# STM32_Decoupling.net
KiCad netlist of a schematic drawn in Altium Designer
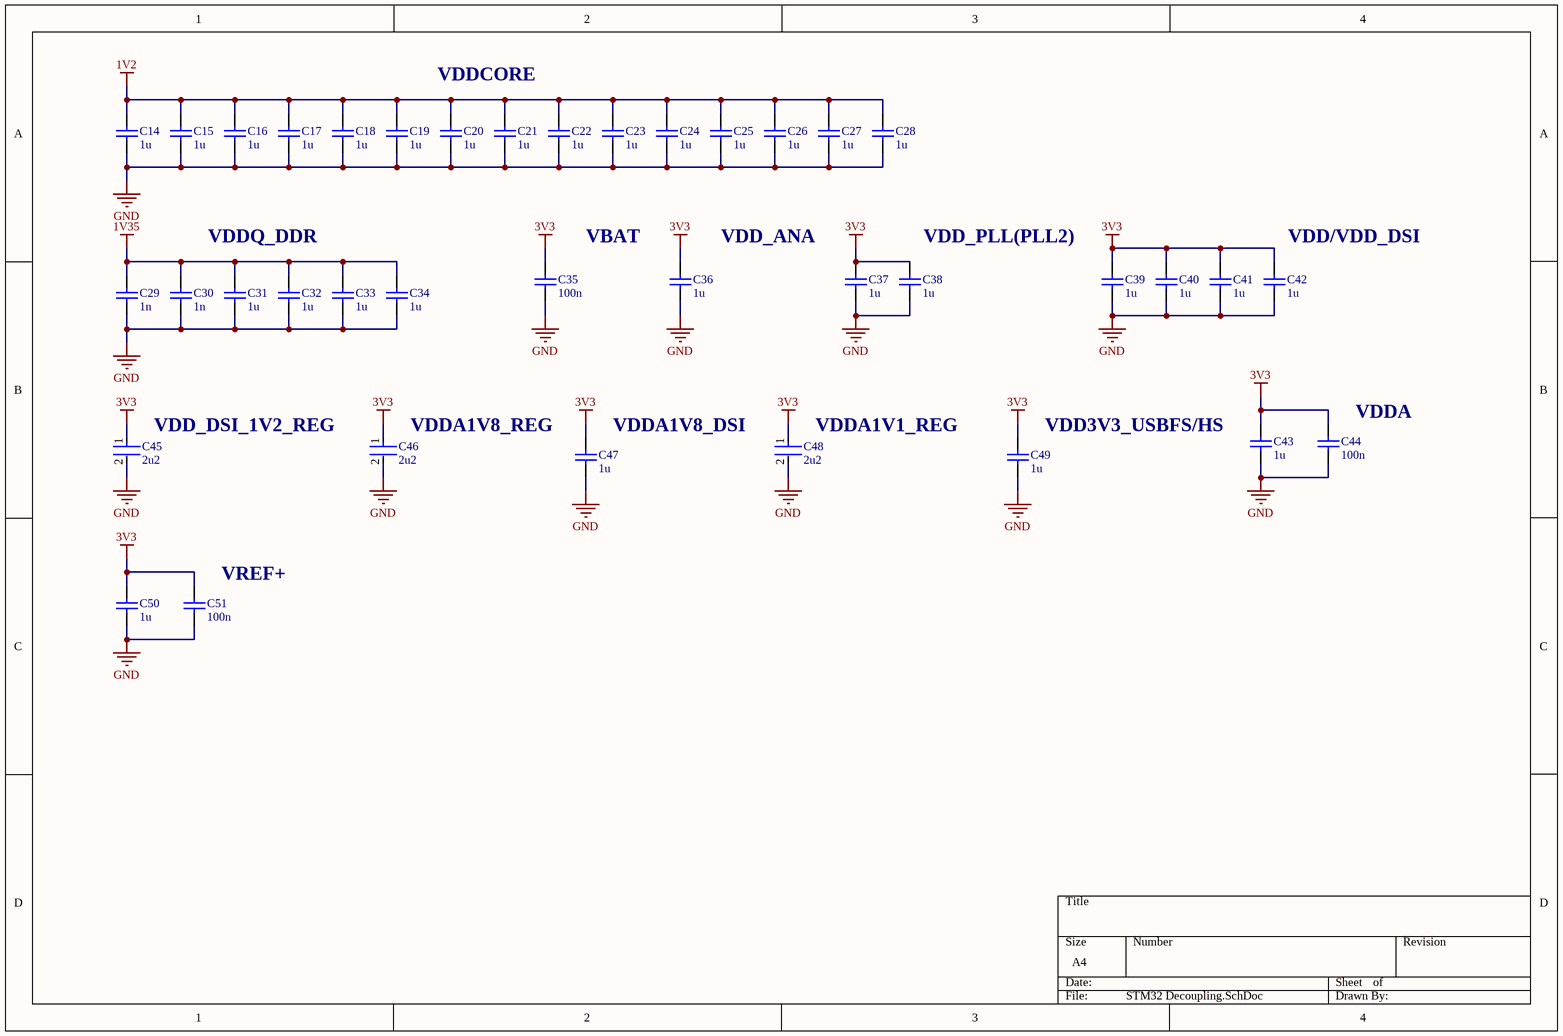
[diagram p0: STM32 Decoupling.SchDoc]

(export (version "E")
  (design (tool "Eeschema 10.0.6"))
  (components
    (comp (ref "C14")
      (value "1u")
      (footprint "CAPC0603X33X15LL03T05")
      (fields
        (field (name "PART NUMBER") "02016D104KAT2A")
        (field (name "MANUFACTURER") "AVX Interconnect / Elco")
      )
      (libsource (lib "Altium Content Vault") (part "CAP"))
    )
    (comp (ref "C15")
      (value "1u")
      (footprint "CAPC0603X33X15LL03T05")
      (fields
        (field (name "PART NUMBER") "02016D104KAT2A")
        (field (name "MANUFACTURER") "AVX Interconnect / Elco")
      )
      (libsource (lib "Altium Content Vault") (part "CAP"))
    )
    (comp (ref "C16")
      (value "1u")
      (footprint "CAPC0603X33X15LL03T05")
      (fields
        (field (name "PART NUMBER") "02016D104KAT2A")
        (field (name "MANUFACTURER") "AVX Interconnect / Elco")
      )
      (libsource (lib "Altium Content Vault") (part "CAP"))
    )
    (comp (ref "C17")
      (value "1u")
      (footprint "CAPC0603X33X15LL03T05")
      (fields
        (field (name "PART NUMBER") "02016D104KAT2A")
        (field (name "MANUFACTURER") "AVX Interconnect / Elco")
      )
      (libsource (lib "Altium Content Vault") (part "CAP"))
    )
    (comp (ref "C18")
      (value "1u")
      (footprint "CAPC0603X33X15LL03T05")
      (fields
        (field (name "PART NUMBER") "02016D104KAT2A")
        (field (name "MANUFACTURER") "AVX Interconnect / Elco")
      )
      (libsource (lib "Altium Content Vault") (part "CAP"))
    )
    (comp (ref "C19")
      (value "1u")
      (footprint "CAPC0603X33X15LL03T05")
      (fields
        (field (name "PART NUMBER") "02016D104KAT2A")
        (field (name "MANUFACTURER") "AVX Interconnect / Elco")
      )
      (libsource (lib "Altium Content Vault") (part "CAP"))
    )
    (comp (ref "C20")
      (value "1u")
      (footprint "CAPC0603X33X15LL03T05")
      (fields
        (field (name "PART NUMBER") "02016D104KAT2A")
        (field (name "MANUFACTURER") "AVX Interconnect / Elco")
      )
      (libsource (lib "Altium Content Vault") (part "CAP"))
    )
    (comp (ref "C21")
      (value "1u")
      (footprint "CAPC0603X33X15LL03T05")
      (fields
        (field (name "PART NUMBER") "02016D104KAT2A")
        (field (name "MANUFACTURER") "AVX Interconnect / Elco")
      )
      (libsource (lib "Altium Content Vault") (part "CAP"))
    )
    (comp (ref "C22")
      (value "1u")
      (footprint "CAPC0603X33X15LL03T05")
      (fields
        (field (name "PART NUMBER") "02016D104KAT2A")
        (field (name "MANUFACTURER") "AVX Interconnect / Elco")
      )
      (libsource (lib "Altium Content Vault") (part "CAP"))
    )
    (comp (ref "C23")
      (value "1u")
      (footprint "CAPC0603X33X15LL03T05")
      (fields
        (field (name "PART NUMBER") "02016D104KAT2A")
        (field (name "MANUFACTURER") "AVX Interconnect / Elco")
      )
      (libsource (lib "Altium Content Vault") (part "CAP"))
    )
    (comp (ref "C24")
      (value "1u")
      (footprint "CAPC0603X33X15LL03T05")
      (fields
        (field (name "PART NUMBER") "02016D104KAT2A")
        (field (name "MANUFACTURER") "AVX Interconnect / Elco")
      )
      (libsource (lib "Altium Content Vault") (part "CAP"))
    )
    (comp (ref "C25")
      (value "1u")
      (footprint "CAPC0603X33X15LL03T05")
      (fields
        (field (name "PART NUMBER") "02016D104KAT2A")
        (field (name "MANUFACTURER") "AVX Interconnect / Elco")
      )
      (libsource (lib "Altium Content Vault") (part "CAP"))
    )
    (comp (ref "C26")
      (value "1u")
      (footprint "CAPC0603X33X15LL03T05")
      (fields
        (field (name "PART NUMBER") "02016D104KAT2A")
        (field (name "MANUFACTURER") "AVX Interconnect / Elco")
      )
      (libsource (lib "Altium Content Vault") (part "CAP"))
    )
    (comp (ref "C27")
      (value "1u")
      (footprint "CAPC0603X33X15LL03T05")
      (fields
        (field (name "PART NUMBER") "02016D104KAT2A")
        (field (name "MANUFACTURER") "AVX Interconnect / Elco")
      )
      (libsource (lib "Altium Content Vault") (part "CAP"))
    )
    (comp (ref "C28")
      (value "1u")
      (footprint "CAPC0603X33X15LL03T05")
      (fields
        (field (name "PART NUMBER") "02016D104KAT2A")
        (field (name "MANUFACTURER") "AVX Interconnect / Elco")
      )
      (libsource (lib "Altium Content Vault") (part "CAP"))
    )
    (comp (ref "C29")
      (value "1n")
      (footprint "CAPC0603X33X15LL03T05")
      (fields
        (field (name "PART NUMBER") "02016D104KAT2A")
        (field (name "MANUFACTURER") "AVX Interconnect / Elco")
      )
      (libsource (lib "Altium Content Vault") (part "CAP"))
    )
    (comp (ref "C30")
      (value "1n")
      (footprint "CAPC0603X33X15LL03T05")
      (fields
        (field (name "PART NUMBER") "02016D104KAT2A")
        (field (name "MANUFACTURER") "AVX Interconnect / Elco")
      )
      (libsource (lib "Altium Content Vault") (part "CAP"))
    )
    (comp (ref "C31")
      (value "1u")
      (footprint "CAPC0603X33X15LL03T05")
      (fields
        (field (name "PART NUMBER") "02016D104KAT2A")
        (field (name "MANUFACTURER") "AVX Interconnect / Elco")
      )
      (libsource (lib "Altium Content Vault") (part "CAP"))
    )
    (comp (ref "C32")
      (value "1u")
      (footprint "CAPC0603X33X15LL03T05")
      (fields
        (field (name "PART NUMBER") "02016D104KAT2A")
        (field (name "MANUFACTURER") "AVX Interconnect / Elco")
      )
      (libsource (lib "Altium Content Vault") (part "CAP"))
    )
    (comp (ref "C33")
      (value "1u")
      (footprint "CAPC0603X33X15LL03T05")
      (fields
        (field (name "PART NUMBER") "02016D104KAT2A")
        (field (name "MANUFACTURER") "AVX Interconnect / Elco")
      )
      (libsource (lib "Altium Content Vault") (part "CAP"))
    )
    (comp (ref "C34")
      (value "1u")
      (footprint "CAPC0603X33X15LL03T05")
      (fields
        (field (name "PART NUMBER") "02016D104KAT2A")
        (field (name "MANUFACTURER") "AVX Interconnect / Elco")
      )
      (libsource (lib "Altium Content Vault") (part "CAP"))
    )
    (comp (ref "C35")
      (value "100n")
      (footprint "CAPC0603X33X15LL03T05")
      (fields
        (field (name "PART NUMBER") "02016D104KAT2A")
        (field (name "MANUFACTURER") "AVX Interconnect / Elco")
      )
      (libsource (lib "Altium Content Vault") (part "CAP"))
    )
    (comp (ref "C36")
      (value "1u")
      (footprint "CAPC0603X33X15LL03T05")
      (fields
        (field (name "PART NUMBER") "02016D104KAT2A")
        (field (name "MANUFACTURER") "AVX Interconnect / Elco")
      )
      (libsource (lib "Altium Content Vault") (part "CAP"))
    )
    (comp (ref "C37")
      (value "1u")
      (footprint "CAPC0603X33X15LL03T05")
      (fields
        (field (name "PART NUMBER") "02016D104KAT2A")
        (field (name "MANUFACTURER") "AVX Interconnect / Elco")
      )
      (libsource (lib "Altium Content Vault") (part "CAP"))
    )
    (comp (ref "C38")
      (value "1u")
      (footprint "CAPC0603X33X15LL03T05")
      (fields
        (field (name "PART NUMBER") "02016D104KAT2A")
        (field (name "MANUFACTURER") "AVX Interconnect / Elco")
      )
      (libsource (lib "Altium Content Vault") (part "CAP"))
    )
    (comp (ref "C39")
      (value "1u")
      (footprint "CAPC0603X33X15LL03T05")
      (fields
        (field (name "PART NUMBER") "02016D104KAT2A")
        (field (name "MANUFACTURER") "AVX Interconnect / Elco")
      )
      (libsource (lib "Altium Content Vault") (part "CAP"))
    )
    (comp (ref "C40")
      (value "1u")
      (footprint "CAPC0603X33X15LL03T05")
      (fields
        (field (name "PART NUMBER") "02016D104KAT2A")
        (field (name "MANUFACTURER") "AVX Interconnect / Elco")
      )
      (libsource (lib "Altium Content Vault") (part "CAP"))
    )
    (comp (ref "C41")
      (value "1u")
      (footprint "CAPC0603X33X15LL03T05")
      (fields
        (field (name "PART NUMBER") "02016D104KAT2A")
        (field (name "MANUFACTURER") "AVX Interconnect / Elco")
      )
      (libsource (lib "Altium Content Vault") (part "CAP"))
    )
    (comp (ref "C42")
      (value "1u")
      (footprint "CAPC0603X33X15LL03T05")
      (fields
        (field (name "PART NUMBER") "02016D104KAT2A")
        (field (name "MANUFACTURER") "AVX Interconnect / Elco")
      )
      (libsource (lib "Altium Content Vault") (part "CAP"))
    )
    (comp (ref "C43")
      (value "1u")
      (footprint "CAPC0603X33X15LL03T05")
      (fields
        (field (name "PART NUMBER") "02016D104KAT2A")
        (field (name "MANUFACTURER") "AVX Interconnect / Elco")
      )
      (libsource (lib "Altium Content Vault") (part "CAP"))
    )
    (comp (ref "C44")
      (value "100n")
      (footprint "CAPC0603X33X15LL03T05")
      (fields
        (field (name "PART NUMBER") "02016D104KAT2A")
        (field (name "MANUFACTURER") "AVX Interconnect / Elco")
      )
      (libsource (lib "Altium Content Vault") (part "CAP"))
    )
    (comp (ref "C45")
      (value "2u2")
      (footprint "FP-C0603C-CF-MFG")
      (description "CAP CER 0.1UF 50V X7R 0603")
      (fields (field (name "TOLERANCE") "0.1") (field (name "MANUFACTURER") "KEMET"))
      (libsource (lib "Altium Content Vault") (part "b4654b650e69147ec39a6b967a45e02"))
    )
    (comp (ref "C46")
      (value "2u2")
      (footprint "FP-C0603C-CF-MFG")
      (description "CAP CER 0.1UF 50V X7R 0603")
      (fields (field (name "TOLERANCE") "0.1") (field (name "MANUFACTURER") "KEMET"))
      (libsource (lib "Altium Content Vault") (part "b4654b650e69147ec39a6b967a45e02"))
    )
    (comp (ref "C47")
      (value "1u")
      (footprint "CAPC0603X33X15LL03T05")
      (fields
        (field (name "PART NUMBER") "02016D104KAT2A")
        (field (name "MANUFACTURER") "AVX Interconnect / Elco")
      )
      (libsource (lib "Altium Content Vault") (part "CAP"))
    )
    (comp (ref "C48")
      (value "2u2")
      (footprint "FP-C0603C-CF-MFG")
      (description "CAP CER 0.1UF 50V X7R 0603")
      (fields (field (name "TOLERANCE") "0.1") (field (name "MANUFACTURER") "KEMET"))
      (libsource (lib "Altium Content Vault") (part "b4654b650e69147ec39a6b967a45e02"))
    )
    (comp (ref "C49")
      (value "1u")
      (footprint "CAPC0603X33X15LL03T05")
      (fields
        (field (name "PART NUMBER") "02016D104KAT2A")
        (field (name "MANUFACTURER") "AVX Interconnect / Elco")
      )
      (libsource (lib "Altium Content Vault") (part "CAP"))
    )
    (comp (ref "C50")
      (value "1u")
      (footprint "CAPC0603X33X15LL03T05")
      (fields
        (field (name "PART NUMBER") "02016D104KAT2A")
        (field (name "MANUFACTURER") "AVX Interconnect / Elco")
      )
      (libsource (lib "Altium Content Vault") (part "CAP"))
    )
    (comp (ref "C51")
      (value "100n")
      (footprint "CAPC0603X33X15LL03T05")
      (fields
        (field (name "PART NUMBER") "02016D104KAT2A")
        (field (name "MANUFACTURER") "AVX Interconnect / Elco")
      )
      (libsource (lib "Altium Content Vault") (part "CAP"))
    )
  )
  (nets
    (net (code "1") (name "1V2") (class "Default")
      (node (ref "C14") (pin "2") (pinfunction "2_2") (pintype "passive"))
      (node (ref "C15") (pin "2") (pinfunction "2_2") (pintype "passive"))
      (node (ref "C16") (pin "2") (pinfunction "2_2") (pintype "passive"))
      (node (ref "C17") (pin "2") (pinfunction "2_2") (pintype "passive"))
      (node (ref "C18") (pin "2") (pinfunction "2_2") (pintype "passive"))
      (node (ref "C19") (pin "2") (pinfunction "2_2") (pintype "passive"))
      (node (ref "C20") (pin "2") (pinfunction "2_2") (pintype "passive"))
      (node (ref "C21") (pin "2") (pinfunction "2_2") (pintype "passive"))
      (node (ref "C22") (pin "2") (pinfunction "2_2") (pintype "passive"))
      (node (ref "C23") (pin "2") (pinfunction "2_2") (pintype "passive"))
      (node (ref "C24") (pin "2") (pinfunction "2_2") (pintype "passive"))
      (node (ref "C25") (pin "2") (pinfunction "2_2") (pintype "passive"))
      (node (ref "C26") (pin "2") (pinfunction "2_2") (pintype "passive"))
      (node (ref "C27") (pin "2") (pinfunction "2_2") (pintype "passive"))
      (node (ref "C28") (pin "2") (pinfunction "2_2") (pintype "passive"))
    )
    (net (code "2") (name "1V35") (class "Default")
      (node (ref "C29") (pin "2") (pinfunction "2_2") (pintype "passive"))
      (node (ref "C30") (pin "2") (pinfunction "2_2") (pintype "passive"))
      (node (ref "C31") (pin "2") (pinfunction "2_2") (pintype "passive"))
      (node (ref "C32") (pin "2") (pinfunction "2_2") (pintype "passive"))
      (node (ref "C33") (pin "2") (pinfunction "2_2") (pintype "passive"))
      (node (ref "C34") (pin "2") (pinfunction "2_2") (pintype "passive"))
    )
    (net (code "3") (name "3V3") (class "Default")
      (node (ref "C35") (pin "2") (pinfunction "2_2") (pintype "passive"))
      (node (ref "C36") (pin "2") (pinfunction "2_2") (pintype "passive"))
      (node (ref "C37") (pin "2") (pinfunction "2_2") (pintype "passive"))
      (node (ref "C38") (pin "2") (pinfunction "2_2") (pintype "passive"))
      (node (ref "C39") (pin "2") (pinfunction "2_2") (pintype "passive"))
      (node (ref "C40") (pin "2") (pinfunction "2_2") (pintype "passive"))
      (node (ref "C41") (pin "2") (pinfunction "2_2") (pintype "passive"))
      (node (ref "C42") (pin "2") (pinfunction "2_2") (pintype "passive"))
      (node (ref "C43") (pin "2") (pinfunction "2_2") (pintype "passive"))
      (node (ref "C44") (pin "2") (pinfunction "2_2") (pintype "passive"))
      (node (ref "C45") (pin "1") (pinfunction "1_1") (pintype "passive"))
      (node (ref "C46") (pin "1") (pinfunction "1_1") (pintype "passive"))
      (node (ref "C47") (pin "2") (pinfunction "2_2") (pintype "passive"))
      (node (ref "C48") (pin "1") (pinfunction "1_1") (pintype "passive"))
      (node (ref "C49") (pin "2") (pinfunction "2_2") (pintype "passive"))
      (node (ref "C50") (pin "2") (pinfunction "2_2") (pintype "passive"))
      (node (ref "C51") (pin "2") (pinfunction "2_2") (pintype "passive"))
    )
    (net (code "4") (name "GND") (class "Default")
      (node (ref "C14") (pin "1") (pinfunction "1_1") (pintype "passive"))
      (node (ref "C15") (pin "1") (pinfunction "1_1") (pintype "passive"))
      (node (ref "C16") (pin "1") (pinfunction "1_1") (pintype "passive"))
      (node (ref "C17") (pin "1") (pinfunction "1_1") (pintype "passive"))
      (node (ref "C18") (pin "1") (pinfunction "1_1") (pintype "passive"))
      (node (ref "C19") (pin "1") (pinfunction "1_1") (pintype "passive"))
      (node (ref "C20") (pin "1") (pinfunction "1_1") (pintype "passive"))
      (node (ref "C21") (pin "1") (pinfunction "1_1") (pintype "passive"))
      (node (ref "C22") (pin "1") (pinfunction "1_1") (pintype "passive"))
      (node (ref "C23") (pin "1") (pinfunction "1_1") (pintype "passive"))
      (node (ref "C24") (pin "1") (pinfunction "1_1") (pintype "passive"))
      (node (ref "C25") (pin "1") (pinfunction "1_1") (pintype "passive"))
      (node (ref "C26") (pin "1") (pinfunction "1_1") (pintype "passive"))
      (node (ref "C27") (pin "1") (pinfunction "1_1") (pintype "passive"))
      (node (ref "C28") (pin "1") (pinfunction "1_1") (pintype "passive"))
      (node (ref "C29") (pin "1") (pinfunction "1_1") (pintype "passive"))
      (node (ref "C30") (pin "1") (pinfunction "1_1") (pintype "passive"))
      (node (ref "C31") (pin "1") (pinfunction "1_1") (pintype "passive"))
      (node (ref "C32") (pin "1") (pinfunction "1_1") (pintype "passive"))
      (node (ref "C33") (pin "1") (pinfunction "1_1") (pintype "passive"))
      (node (ref "C34") (pin "1") (pinfunction "1_1") (pintype "passive"))
      (node (ref "C35") (pin "1") (pinfunction "1_1") (pintype "passive"))
      (node (ref "C36") (pin "1") (pinfunction "1_1") (pintype "passive"))
      (node (ref "C37") (pin "1") (pinfunction "1_1") (pintype "passive"))
      (node (ref "C38") (pin "1") (pinfunction "1_1") (pintype "passive"))
      (node (ref "C39") (pin "1") (pinfunction "1_1") (pintype "passive"))
      (node (ref "C40") (pin "1") (pinfunction "1_1") (pintype "passive"))
      (node (ref "C41") (pin "1") (pinfunction "1_1") (pintype "passive"))
      (node (ref "C42") (pin "1") (pinfunction "1_1") (pintype "passive"))
      (node (ref "C43") (pin "1") (pinfunction "1_1") (pintype "passive"))
      (node (ref "C44") (pin "1") (pinfunction "1_1") (pintype "passive"))
      (node (ref "C45") (pin "2") (pinfunction "2_2") (pintype "passive"))
      (node (ref "C46") (pin "2") (pinfunction "2_2") (pintype "passive"))
      (node (ref "C47") (pin "1") (pinfunction "1_1") (pintype "passive"))
      (node (ref "C48") (pin "2") (pinfunction "2_2") (pintype "passive"))
      (node (ref "C49") (pin "1") (pinfunction "1_1") (pintype "passive"))
      (node (ref "C50") (pin "1") (pinfunction "1_1") (pintype "passive"))
      (node (ref "C51") (pin "1") (pinfunction "1_1") (pintype "passive"))
    )
  )
)
